# SkinProc_v0_1b.net
KiCad netlist of a schematic drawn in EAGLE
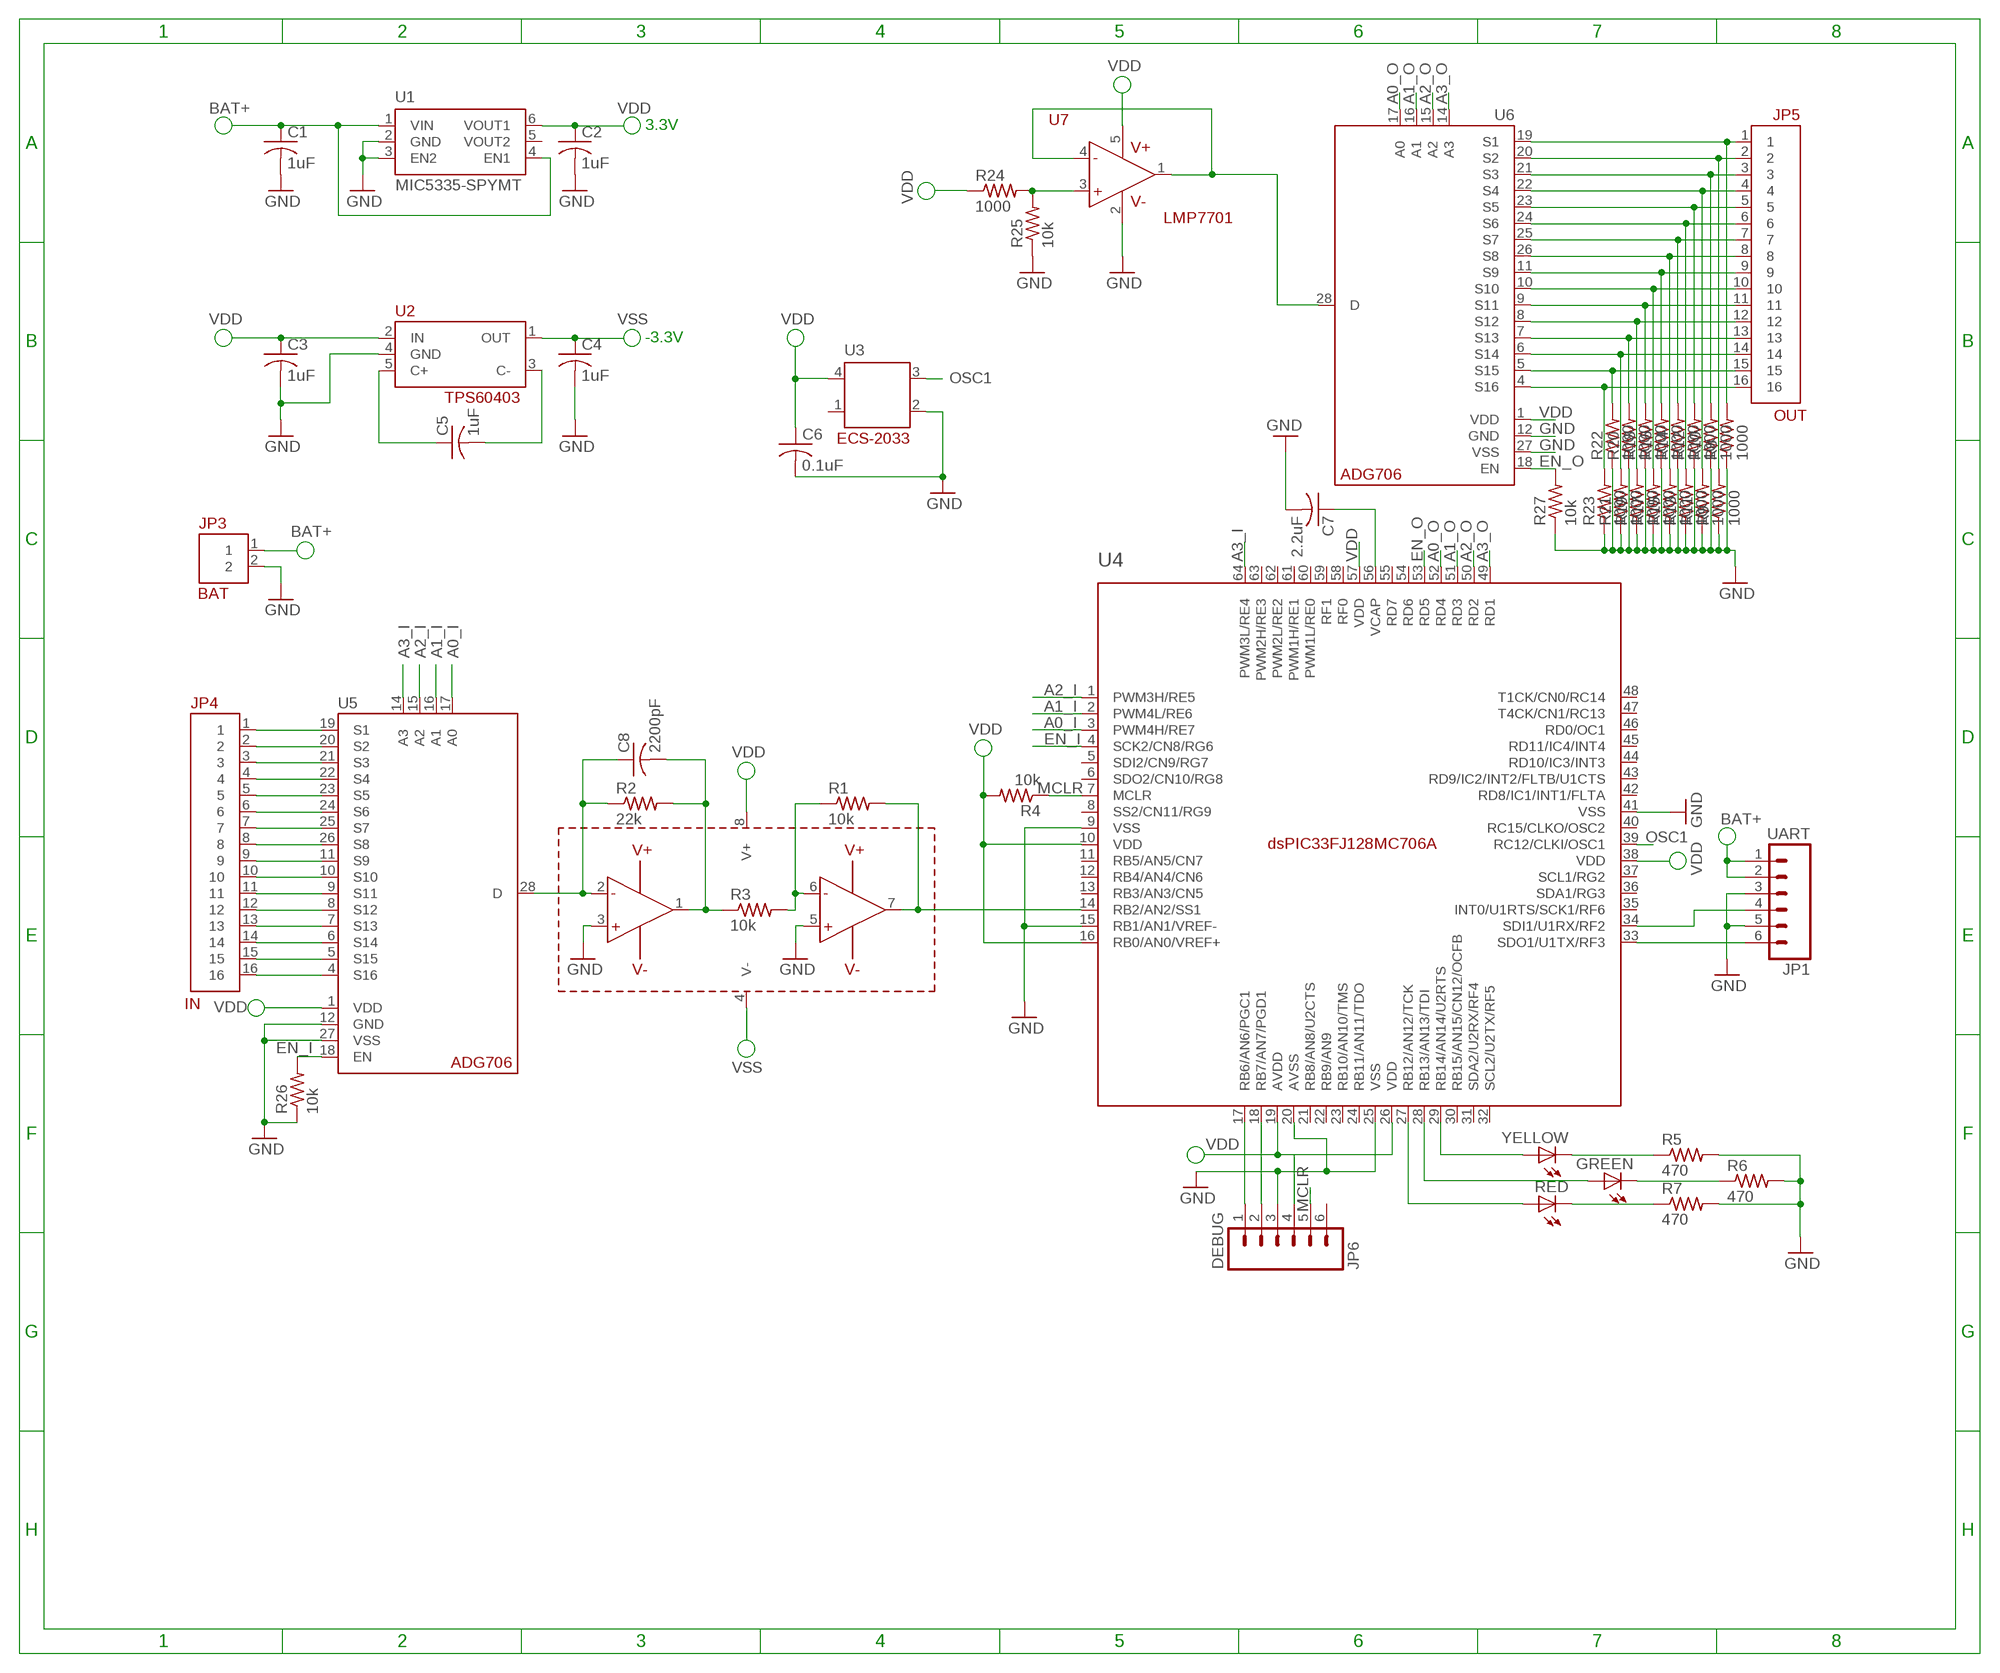
[diagram p0: schematic, sheet 1]

(export (version "E")
  (design (tool "Eeschema 10.0.6"))
  (components
    (comp (ref "C1")
      (value "1uF")
      (footprint "eagle-import:C0402")
      (libsource (lib "eagle-import") (part "C-USC0402"))
    )
    (comp (ref "C2")
      (value "1uF")
      (footprint "eagle-import:C0402")
      (libsource (lib "eagle-import") (part "C-USC0402"))
    )
    (comp (ref "C3")
      (value "1uF")
      (footprint "eagle-import:C0402")
      (libsource (lib "eagle-import") (part "C-USC0402"))
    )
    (comp (ref "C4")
      (value "1uF")
      (footprint "eagle-import:C0402")
      (libsource (lib "eagle-import") (part "C-USC0402"))
    )
    (comp (ref "C5")
      (value "1uF")
      (footprint "eagle-import:C0402")
      (libsource (lib "eagle-import") (part "C-USC0402"))
    )
    (comp (ref "C6")
      (value "0.1uF")
      (footprint "eagle-import:C0402")
      (libsource (lib "eagle-import") (part "C-USC0402"))
    )
    (comp (ref "C7")
      (value "2.2uF")
      (footprint "eagle-import:C0402")
      (libsource (lib "eagle-import") (part "C-USC0402"))
    )
    (comp (ref "C8")
      (value "2200pF")
      (footprint "eagle-import:C0402")
      (libsource (lib "eagle-import") (part "C-USC0402"))
    )
    (comp (ref "GREEN")
      (value "LEDCHIP-LED0603")
      (footprint "eagle-import:CHIP-LED0603")
      (libsource (lib "eagle-import") (part "LEDCHIP-LED0603"))
    )
    (comp (ref "JP1")
      (value "UART")
      (footprint "eagle-import:MOLEX_503480-0600")
      (libsource (lib "eagle-import") (part "MOLEX_503480-0600"))
    )
    (comp (ref "JP3")
      (value "BAT")
      (footprint "eagle-import:2_PAD")
      (libsource (lib "eagle-import") (part "2_PAD"))
    )
    (comp (ref "JP4")
      (value "IN")
      (footprint "eagle-import:16_PAD")
      (libsource (lib "eagle-import") (part "16_PAD"))
    )
    (comp (ref "JP5")
      (value "OUT")
      (footprint "eagle-import:16_PAD")
      (libsource (lib "eagle-import") (part "16_PAD"))
    )
    (comp (ref "JP6")
      (value "DEBUG")
      (footprint "eagle-import:MOLEX_503480-0600")
      (libsource (lib "eagle-import") (part "MOLEX_503480-0600"))
    )
    (comp (ref "R1")
      (value "10k")
      (footprint "eagle-import:R0402")
      (libsource (lib "eagle-import") (part "R-US_R0402"))
    )
    (comp (ref "R2")
      (value "22k")
      (footprint "eagle-import:R0402")
      (libsource (lib "eagle-import") (part "R-US_R0402"))
    )
    (comp (ref "R3")
      (value "10k")
      (footprint "eagle-import:R0402")
      (libsource (lib "eagle-import") (part "R-US_R0402"))
    )
    (comp (ref "R4")
      (value "10k")
      (footprint "eagle-import:R0402")
      (libsource (lib "eagle-import") (part "R-US_R0402"))
    )
    (comp (ref "R5")
      (value "470")
      (footprint "eagle-import:R0402")
      (libsource (lib "eagle-import") (part "R-US_R0402"))
    )
    (comp (ref "R6")
      (value "470")
      (footprint "eagle-import:R0402")
      (libsource (lib "eagle-import") (part "R-US_R0402"))
    )
    (comp (ref "R7")
      (value "470")
      (footprint "eagle-import:R0402")
      (libsource (lib "eagle-import") (part "R-US_R0402"))
    )
    (comp (ref "R8")
      (value "1000")
      (footprint "eagle-import:R0402")
      (libsource (lib "eagle-import") (part "R-US_R0402"))
    )
    (comp (ref "R9")
      (value "1000")
      (footprint "eagle-import:R0402")
      (libsource (lib "eagle-import") (part "R-US_R0402"))
    )
    (comp (ref "R10")
      (value "1000")
      (footprint "eagle-import:R0402")
      (libsource (lib "eagle-import") (part "R-US_R0402"))
    )
    (comp (ref "R11")
      (value "1000")
      (footprint "eagle-import:R0402")
      (libsource (lib "eagle-import") (part "R-US_R0402"))
    )
    (comp (ref "R12")
      (value "1000")
      (footprint "eagle-import:R0402")
      (libsource (lib "eagle-import") (part "R-US_R0402"))
    )
    (comp (ref "R13")
      (value "1000")
      (footprint "eagle-import:R0402")
      (libsource (lib "eagle-import") (part "R-US_R0402"))
    )
    (comp (ref "R14")
      (value "1000")
      (footprint "eagle-import:R0402")
      (libsource (lib "eagle-import") (part "R-US_R0402"))
    )
    (comp (ref "R15")
      (value "1000")
      (footprint "eagle-import:R0402")
      (libsource (lib "eagle-import") (part "R-US_R0402"))
    )
    (comp (ref "R16")
      (value "1000")
      (footprint "eagle-import:R0402")
      (libsource (lib "eagle-import") (part "R-US_R0402"))
    )
    (comp (ref "R17")
      (value "1000")
      (footprint "eagle-import:R0402")
      (libsource (lib "eagle-import") (part "R-US_R0402"))
    )
    (comp (ref "R18")
      (value "1000")
      (footprint "eagle-import:R0402")
      (libsource (lib "eagle-import") (part "R-US_R0402"))
    )
    (comp (ref "R19")
      (value "1000")
      (footprint "eagle-import:R0402")
      (libsource (lib "eagle-import") (part "R-US_R0402"))
    )
    (comp (ref "R20")
      (value "1000")
      (footprint "eagle-import:R0402")
      (libsource (lib "eagle-import") (part "R-US_R0402"))
    )
    (comp (ref "R21")
      (value "1000")
      (footprint "eagle-import:R0402")
      (libsource (lib "eagle-import") (part "R-US_R0402"))
    )
    (comp (ref "R22")
      (value "1000")
      (footprint "eagle-import:R0402")
      (libsource (lib "eagle-import") (part "R-US_R0402"))
    )
    (comp (ref "R23")
      (value "1000")
      (footprint "eagle-import:R0402")
      (libsource (lib "eagle-import") (part "R-US_R0402"))
    )
    (comp (ref "R24")
      (value "1000")
      (footprint "eagle-import:R0402")
      (libsource (lib "eagle-import") (part "R-US_R0402"))
    )
    (comp (ref "R25")
      (value "10k")
      (footprint "eagle-import:R0402")
      (libsource (lib "eagle-import") (part "R-US_R0402"))
    )
    (comp (ref "R26")
      (value "10k")
      (footprint "eagle-import:R0402")
      (libsource (lib "eagle-import") (part "R-US_R0402"))
    )
    (comp (ref "R27")
      (value "10k")
      (footprint "eagle-import:R0402")
      (libsource (lib "eagle-import") (part "R-US_R0402"))
    )
    (comp (ref "RED")
      (value "LEDCHIP-LED0603")
      (footprint "eagle-import:CHIP-LED0603")
      (libsource (lib "eagle-import") (part "LEDCHIP-LED0603"))
    )
    (comp (ref "U1")
      (value "MIC5335-SPYMT")
      (footprint "eagle-import:MLF-6")
      (libsource (lib "eagle-import") (part "MIC5320-JGYML"))
    )
    (comp (ref "U2")
      (value "TPS60403")
      (footprint "eagle-import:SOT23-DBV")
      (libsource (lib "eagle-import") (part "TPS60403"))
    )
    (comp (ref "U3")
      (value "OSCILLATORS")
      (footprint "eagle-import:OSCILLATOR-SMD")
      (libsource (lib "eagle-import") (part "OSCILLATORS"))
    )
    (comp (ref "U4")
      (value "DSPIC33FJ128MC706-I/PT")
      (footprint "eagle-import:TQFP64")
      (libsource (lib "eagle-import") (part "DSPIC33FJ128MC706-I/PT"))
    )
    (comp (ref "U5")
      (value "ADG706")
      (footprint "eagle-import:TSSOP28")
      (libsource (lib "eagle-import") (part "ADG706"))
    )
    (comp (ref "U6")
      (value "ADG706")
      (footprint "eagle-import:TSSOP28")
      (libsource (lib "eagle-import") (part "ADG706"))
    )
    (comp (ref "U7")
      (value "LMP7701")
      (footprint "eagle-import:SOT23-DBV")
      (libsource (lib "eagle-import") (part "NATIONAL_OP_AMP_SINGLE"))
    )
    (comp (ref "U8")
      (value "NATIONAL_OP_AMP")
      (footprint "eagle-import:SO08")
      (libsource (lib "eagle-import") (part "NATIONAL_OP_AMP"))
    )
    (comp (ref "YELLOW")
      (value "LEDCHIP-LED0603")
      (footprint "eagle-import:CHIP-LED0603")
      (libsource (lib "eagle-import") (part "LEDCHIP-LED0603"))
    )
  )
  (nets
    (net (code "1") (name "/A0_I") (class "Default")
      (node (ref "U4") (pin "3") (pinfunction "PWM4H/RE7_3") (pintype "bidirectional"))
      (node (ref "U5") (pin "17") (pinfunction "A0_17") (pintype "bidirectional"))
    )
    (net (code "2") (name "/A0_O") (class "Default")
      (node (ref "U4") (pin "52") (pinfunction "RD4_52") (pintype "bidirectional"))
      (node (ref "U6") (pin "17") (pinfunction "A0_17") (pintype "bidirectional"))
    )
    (net (code "3") (name "/A1_I") (class "Default")
      (node (ref "U4") (pin "2") (pinfunction "PWM4L/RE6_2") (pintype "bidirectional"))
      (node (ref "U5") (pin "16") (pinfunction "A1_16") (pintype "bidirectional"))
    )
    (net (code "4") (name "/A1_O") (class "Default")
      (node (ref "U4") (pin "51") (pinfunction "RD3_51") (pintype "bidirectional"))
      (node (ref "U6") (pin "16") (pinfunction "A1_16") (pintype "bidirectional"))
    )
    (net (code "5") (name "/A2_I") (class "Default")
      (node (ref "U4") (pin "1") (pinfunction "PWM3H/RE5_1") (pintype "bidirectional"))
      (node (ref "U5") (pin "15") (pinfunction "A2_15") (pintype "bidirectional"))
    )
    (net (code "6") (name "/A2_O") (class "Default")
      (node (ref "U4") (pin "50") (pinfunction "RD2_50") (pintype "bidirectional"))
      (node (ref "U6") (pin "15") (pinfunction "A2_15") (pintype "bidirectional"))
    )
    (net (code "7") (name "/A3_I") (class "Default")
      (node (ref "U4") (pin "64") (pinfunction "PWM3L/RE4_64") (pintype "bidirectional"))
      (node (ref "U5") (pin "14") (pinfunction "A3_14") (pintype "bidirectional"))
    )
    (net (code "8") (name "/A3_O") (class "Default")
      (node (ref "U4") (pin "49") (pinfunction "RD1_49") (pintype "bidirectional"))
      (node (ref "U6") (pin "14") (pinfunction "A3_14") (pintype "bidirectional"))
    )
    (net (code "9") (name "/BAT+") (class "Default")
      (node (ref "C1") (pin "1") (pinfunction "1_1") (pintype "passive"))
      (node (ref "JP1") (pin "1") (pinfunction "1_1") (pintype "passive"))
      (node (ref "JP1") (pin "2") (pinfunction "2_2") (pintype "passive"))
      (node (ref "JP3") (pin "1") (pinfunction "1_1") (pintype "bidirectional"))
      (node (ref "U1") (pin "1") (pinfunction "VIN_1") (pintype "bidirectional"))
      (node (ref "U1") (pin "4") (pinfunction "EN1_4") (pintype "bidirectional"))
    )
    (net (code "10") (name "/EN_I") (class "Default")
      (node (ref "R26") (pin "2") (pinfunction "2_2") (pintype "passive"))
      (node (ref "U4") (pin "4") (pinfunction "SCK2/CN8/RG6_4") (pintype "bidirectional"))
      (node (ref "U5") (pin "18") (pinfunction "EN_18") (pintype "bidirectional"))
    )
    (net (code "11") (name "/EN_O") (class "Default")
      (node (ref "R27") (pin "2") (pinfunction "2_2") (pintype "passive"))
      (node (ref "U4") (pin "53") (pinfunction "RD5_53") (pintype "bidirectional"))
      (node (ref "U6") (pin "18") (pinfunction "EN_18") (pintype "bidirectional"))
    )
    (net (code "12") (name "/MCLR") (class "Default")
      (node (ref "JP6") (pin "5") (pinfunction "5_5") (pintype "passive"))
      (node (ref "R4") (pin "1") (pinfunction "1_1") (pintype "passive"))
      (node (ref "U4") (pin "7") (pinfunction "MCLR_7") (pintype "input"))
    )
    (net (code "13") (name "/OSC1") (class "Default")
      (node (ref "U3") (pin "3") (pinfunction "OUT_3") (pintype "bidirectional"))
      (node (ref "U4") (pin "39") (pinfunction "RC12/CLKI/OSC1_39") (pintype "bidirectional"))
    )
    (net (code "14") (name "/VDD") (class "Default")
      (node (ref "C2") (pin "1") (pinfunction "1_1") (pintype "passive"))
      (node (ref "C3") (pin "1") (pinfunction "1_1") (pintype "passive"))
      (node (ref "C6") (pin "1") (pinfunction "1_1") (pintype "passive"))
      (node (ref "JP6") (pin "4") (pinfunction "4_4") (pintype "passive"))
      (node (ref "R24") (pin "1") (pinfunction "1_1") (pintype "passive"))
      (node (ref "R4") (pin "2") (pinfunction "2_2") (pintype "passive"))
      (node (ref "U1") (pin "6") (pinfunction "VOUT1_6") (pintype "bidirectional"))
      (node (ref "U2") (pin "2") (pinfunction "IN_2") (pintype "bidirectional"))
      (node (ref "U3") (pin "4") (pinfunction "VDD_4") (pintype "bidirectional"))
      (node (ref "U4") (pin "10") (pinfunction "VDD_10") (pintype "power_in"))
      (node (ref "U4") (pin "16") (pinfunction "RB0/AN0/VREF+_16") (pintype "bidirectional"))
      (node (ref "U4") (pin "19") (pinfunction "AVDD_19") (pintype "power_in"))
      (node (ref "U4") (pin "26") (pinfunction "VDD_26") (pintype "power_in"))
      (node (ref "U4") (pin "38") (pinfunction "VDD_38") (pintype "power_in"))
      (node (ref "U4") (pin "57") (pinfunction "VDD_57") (pintype "power_in"))
      (node (ref "U5") (pin "1") (pinfunction "VDD_1") (pintype "bidirectional"))
      (node (ref "U6") (pin "1") (pinfunction "VDD_1") (pintype "bidirectional"))
      (node (ref "U7") (pin "5") (pinfunction "V+_5") (pintype "bidirectional"))
      (node (ref "U8") (pin "8") (pinfunction "V+_8") (pintype "bidirectional"))
    )
    (net (code "15") (name "/VSS") (class "Default")
      (node (ref "C4") (pin "1") (pinfunction "1_1") (pintype "passive"))
      (node (ref "U2") (pin "1") (pinfunction "OUT_1") (pintype "bidirectional"))
      (node (ref "U8") (pin "4") (pinfunction "V-_4") (pintype "bidirectional"))
    )
    (net (code "16") (name "GND") (class "Default")
      (node (ref "C1") (pin "2") (pinfunction "2_2") (pintype "passive"))
      (node (ref "C2") (pin "2") (pinfunction "2_2") (pintype "passive"))
      (node (ref "C3") (pin "2") (pinfunction "2_2") (pintype "passive"))
      (node (ref "C4") (pin "2") (pinfunction "2_2") (pintype "passive"))
      (node (ref "C6") (pin "2") (pinfunction "2_2") (pintype "passive"))
      (node (ref "C7") (pin "2") (pinfunction "2_2") (pintype "passive"))
      (node (ref "JP1") (pin "3") (pinfunction "3_3") (pintype "passive"))
      (node (ref "JP1") (pin "5") (pinfunction "5_5") (pintype "passive"))
      (node (ref "JP3") (pin "2") (pinfunction "2_2") (pintype "bidirectional"))
      (node (ref "JP6") (pin "3") (pinfunction "3_3") (pintype "passive"))
      (node (ref "R10") (pin "1") (pinfunction "1_1") (pintype "passive"))
      (node (ref "R11") (pin "1") (pinfunction "1_1") (pintype "passive"))
      (node (ref "R12") (pin "1") (pinfunction "1_1") (pintype "passive"))
      (node (ref "R13") (pin "1") (pinfunction "1_1") (pintype "passive"))
      (node (ref "R14") (pin "1") (pinfunction "1_1") (pintype "passive"))
      (node (ref "R15") (pin "1") (pinfunction "1_1") (pintype "passive"))
      (node (ref "R16") (pin "1") (pinfunction "1_1") (pintype "passive"))
      (node (ref "R17") (pin "1") (pinfunction "1_1") (pintype "passive"))
      (node (ref "R18") (pin "1") (pinfunction "1_1") (pintype "passive"))
      (node (ref "R19") (pin "1") (pinfunction "1_1") (pintype "passive"))
      (node (ref "R20") (pin "1") (pinfunction "1_1") (pintype "passive"))
      (node (ref "R21") (pin "1") (pinfunction "1_1") (pintype "passive"))
      (node (ref "R22") (pin "1") (pinfunction "1_1") (pintype "passive"))
      (node (ref "R23") (pin "1") (pinfunction "1_1") (pintype "passive"))
      (node (ref "R25") (pin "1") (pinfunction "1_1") (pintype "passive"))
      (node (ref "R26") (pin "1") (pinfunction "1_1") (pintype "passive"))
      (node (ref "R27") (pin "1") (pinfunction "1_1") (pintype "passive"))
      (node (ref "R5") (pin "2") (pinfunction "2_2") (pintype "passive"))
      (node (ref "R6") (pin "2") (pinfunction "2_2") (pintype "passive"))
      (node (ref "R7") (pin "2") (pinfunction "2_2") (pintype "passive"))
      (node (ref "R8") (pin "1") (pinfunction "1_1") (pintype "passive"))
      (node (ref "R9") (pin "1") (pinfunction "1_1") (pintype "passive"))
      (node (ref "U1") (pin "2") (pinfunction "GND_2") (pintype "bidirectional"))
      (node (ref "U1") (pin "3") (pinfunction "EN2_3") (pintype "bidirectional"))
      (node (ref "U2") (pin "4") (pinfunction "GND_4") (pintype "bidirectional"))
      (node (ref "U3") (pin "2") (pinfunction "GND_2") (pintype "bidirectional"))
      (node (ref "U4") (pin "15") (pinfunction "RB1/AN1/VREF-_15") (pintype "bidirectional"))
      (node (ref "U4") (pin "20") (pinfunction "AVSS_20") (pintype "power_in"))
      (node (ref "U4") (pin "25") (pinfunction "VSS_25") (pintype "power_in"))
      (node (ref "U4") (pin "41") (pinfunction "VSS_41") (pintype "power_in"))
      (node (ref "U4") (pin "9") (pinfunction "VSS_9") (pintype "power_in"))
      (node (ref "U5") (pin "12") (pinfunction "GND_12") (pintype "bidirectional"))
      (node (ref "U5") (pin "27") (pinfunction "VSS_27") (pintype "bidirectional"))
      (node (ref "U6") (pin "12") (pinfunction "GND_12") (pintype "bidirectional"))
      (node (ref "U6") (pin "27") (pinfunction "VSS_27") (pintype "bidirectional"))
      (node (ref "U7") (pin "2") (pinfunction "V-_2") (pintype "bidirectional"))
      (node (ref "U8") (pin "3") (pinfunction "+A_3") (pintype "bidirectional"))
      (node (ref "U8") (pin "5") (pinfunction "+B_5") (pintype "bidirectional"))
    )
    (net (code "17") (name "Net-(GREEN-PadC)") (class "Default")
      (node (ref "GREEN") (pin "C") (pinfunction "C_C") (pintype "passive"))
      (node (ref "R6") (pin "1") (pinfunction "1_1") (pintype "passive"))
    )
    (net (code "18") (name "Net-(R5-Pad1)") (class "Default")
      (node (ref "R5") (pin "1") (pinfunction "1_1") (pintype "passive"))
      (node (ref "YELLOW") (pin "C") (pinfunction "C_C") (pintype "passive"))
    )
    (net (code "19") (name "Net-(R7-Pad1)") (class "Default")
      (node (ref "R7") (pin "1") (pinfunction "1_1") (pintype "passive"))
      (node (ref "RED") (pin "C") (pinfunction "C_C") (pintype "passive"))
    )
    (net (code "20") (name "Net-(U2-C+)") (class "Default")
      (node (ref "C5") (pin "1") (pinfunction "1_1") (pintype "passive"))
      (node (ref "U2") (pin "5") (pinfunction "C+_5") (pintype "bidirectional"))
    )
    (net (code "21") (name "Net-(U2-C-)") (class "Default")
      (node (ref "C5") (pin "2") (pinfunction "2_2") (pintype "passive"))
      (node (ref "U2") (pin "3") (pinfunction "C-_3") (pintype "bidirectional"))
    )
    (net (code "22") (name "Net-(U4-RB2{slash}AN2{slash}SS1)") (class "Default")
      (node (ref "R1") (pin "2") (pinfunction "2_2") (pintype "passive"))
      (node (ref "U4") (pin "14") (pinfunction "RB2/AN2/SS1_14") (pintype "bidirectional"))
      (node (ref "U8") (pin "7") (pinfunction "VOUTB_7") (pintype "bidirectional"))
    )
    (net (code "23") (name "Net-(U4-RB6{slash}AN6{slash}PGC1)") (class "Default")
      (node (ref "JP6") (pin "1") (pinfunction "1_1") (pintype "passive"))
      (node (ref "U4") (pin "17") (pinfunction "RB6/AN6/PGC1_17") (pintype "bidirectional"))
    )
    (net (code "24") (name "Net-(U4-RB7{slash}AN7{slash}PGD1)") (class "Default")
      (node (ref "JP6") (pin "2") (pinfunction "2_2") (pintype "passive"))
      (node (ref "U4") (pin "18") (pinfunction "RB7/AN7/PGD1_18") (pintype "bidirectional"))
    )
    (net (code "25") (name "Net-(U4-RB12{slash}AN12{slash}TCK)") (class "Default")
      (node (ref "RED") (pin "A") (pinfunction "A_A") (pintype "passive"))
      (node (ref "U4") (pin "27") (pinfunction "RB12/AN12/TCK_27") (pintype "bidirectional"))
    )
    (net (code "26") (name "Net-(U4-RB13{slash}AN13{slash}TDI)") (class "Default")
      (node (ref "GREEN") (pin "A") (pinfunction "A_A") (pintype "passive"))
      (node (ref "U4") (pin "28") (pinfunction "RB13/AN13/TDI_28") (pintype "bidirectional"))
    )
    (net (code "27") (name "Net-(U4-RB14{slash}AN14{slash}U2RTS)") (class "Default")
      (node (ref "U4") (pin "29") (pinfunction "RB14/AN14/U2RTS_29") (pintype "bidirectional"))
      (node (ref "YELLOW") (pin "A") (pinfunction "A_A") (pintype "passive"))
    )
    (net (code "28") (name "Net-(U4-SDI1{slash}U1RX{slash}RF2)") (class "Default")
      (node (ref "JP1") (pin "4") (pinfunction "4_4") (pintype "passive"))
      (node (ref "U4") (pin "34") (pinfunction "SDI1/U1RX/RF2_34") (pintype "bidirectional"))
    )
    (net (code "29") (name "Net-(U4-SDO1{slash}U1TX{slash}RF3)") (class "Default")
      (node (ref "JP1") (pin "6") (pinfunction "6_6") (pintype "passive"))
      (node (ref "U4") (pin "33") (pinfunction "SDO1/U1TX/RF3_33") (pintype "bidirectional"))
    )
    (net (code "30") (name "Net-(U4-VCAP)") (class "Default")
      (node (ref "C7") (pin "1") (pinfunction "1_1") (pintype "passive"))
      (node (ref "U4") (pin "56") (pinfunction "VCAP_56") (pintype "power_in"))
    )
    (net (code "31") (name "Net-(U5-D)") (class "Default")
      (node (ref "C8") (pin "1") (pinfunction "1_1") (pintype "passive"))
      (node (ref "R2") (pin "1") (pinfunction "1_1") (pintype "passive"))
      (node (ref "U5") (pin "28") (pinfunction "D_28") (pintype "bidirectional"))
      (node (ref "U8") (pin "2") (pinfunction "-A_2") (pintype "bidirectional"))
    )
    (net (code "32") (name "Net-(U5-S1)") (class "Default")
      (node (ref "JP4") (pin "1") (pinfunction "1_1") (pintype "bidirectional"))
      (node (ref "U5") (pin "19") (pinfunction "S1_19") (pintype "bidirectional"))
    )
    (net (code "33") (name "Net-(U5-S2)") (class "Default")
      (node (ref "JP4") (pin "2") (pinfunction "2_2") (pintype "bidirectional"))
      (node (ref "U5") (pin "20") (pinfunction "S2_20") (pintype "bidirectional"))
    )
    (net (code "34") (name "Net-(U5-S3)") (class "Default")
      (node (ref "JP4") (pin "3") (pinfunction "3_3") (pintype "bidirectional"))
      (node (ref "U5") (pin "21") (pinfunction "S3_21") (pintype "bidirectional"))
    )
    (net (code "35") (name "Net-(U5-S4)") (class "Default")
      (node (ref "JP4") (pin "4") (pinfunction "4_4") (pintype "bidirectional"))
      (node (ref "U5") (pin "22") (pinfunction "S4_22") (pintype "bidirectional"))
    )
    (net (code "36") (name "Net-(U5-S5)") (class "Default")
      (node (ref "JP4") (pin "5") (pinfunction "5_5") (pintype "bidirectional"))
      (node (ref "U5") (pin "23") (pinfunction "S5_23") (pintype "bidirectional"))
    )
    (net (code "37") (name "Net-(U5-S6)") (class "Default")
      (node (ref "JP4") (pin "6") (pinfunction "6_6") (pintype "bidirectional"))
      (node (ref "U5") (pin "24") (pinfunction "S6_24") (pintype "bidirectional"))
    )
    (net (code "38") (name "Net-(U5-S7)") (class "Default")
      (node (ref "JP4") (pin "7") (pinfunction "7_7") (pintype "bidirectional"))
      (node (ref "U5") (pin "25") (pinfunction "S7_25") (pintype "bidirectional"))
    )
    (net (code "39") (name "Net-(U5-S8)") (class "Default")
      (node (ref "JP4") (pin "8") (pinfunction "8_8") (pintype "bidirectional"))
      (node (ref "U5") (pin "26") (pinfunction "S8_26") (pintype "bidirectional"))
    )
    (net (code "40") (name "Net-(U5-S9)") (class "Default")
      (node (ref "JP4") (pin "9") (pinfunction "9_9") (pintype "bidirectional"))
      (node (ref "U5") (pin "11") (pinfunction "S9_11") (pintype "bidirectional"))
    )
    (net (code "41") (name "Net-(U5-S10)") (class "Default")
      (node (ref "JP4") (pin "10") (pinfunction "10_10") (pintype "bidirectional"))
      (node (ref "U5") (pin "10") (pinfunction "S10_10") (pintype "bidirectional"))
    )
    (net (code "42") (name "Net-(U5-S11)") (class "Default")
      (node (ref "JP4") (pin "11") (pinfunction "11_11") (pintype "bidirectional"))
      (node (ref "U5") (pin "9") (pinfunction "S11_9") (pintype "bidirectional"))
    )
    (net (code "43") (name "Net-(U5-S12)") (class "Default")
      (node (ref "JP4") (pin "12") (pinfunction "12_12") (pintype "bidirectional"))
      (node (ref "U5") (pin "8") (pinfunction "S12_8") (pintype "bidirectional"))
    )
    (net (code "44") (name "Net-(U5-S13)") (class "Default")
      (node (ref "JP4") (pin "13") (pinfunction "13_13") (pintype "bidirectional"))
      (node (ref "U5") (pin "7") (pinfunction "S13_7") (pintype "bidirectional"))
    )
    (net (code "45") (name "Net-(U5-S14)") (class "Default")
      (node (ref "JP4") (pin "14") (pinfunction "14_14") (pintype "bidirectional"))
      (node (ref "U5") (pin "6") (pinfunction "S14_6") (pintype "bidirectional"))
    )
    (net (code "46") (name "Net-(U5-S15)") (class "Default")
      (node (ref "JP4") (pin "15") (pinfunction "15_15") (pintype "bidirectional"))
      (node (ref "U5") (pin "5") (pinfunction "S15_5") (pintype "bidirectional"))
    )
    (net (code "47") (name "Net-(U5-S16)") (class "Default")
      (node (ref "JP4") (pin "16") (pinfunction "16_16") (pintype "bidirectional"))
      (node (ref "U5") (pin "4") (pinfunction "S16_4") (pintype "bidirectional"))
    )
    (net (code "48") (name "Net-(U6-D)") (class "Default")
      (node (ref "U6") (pin "28") (pinfunction "D_28") (pintype "bidirectional"))
      (node (ref "U7") (pin "1") (pinfunction "VOUT_1") (pintype "bidirectional"))
      (node (ref "U7") (pin "4") (pinfunction "-_4") (pintype "bidirectional"))
    )
    (net (code "49") (name "Net-(U6-S1)") (class "Default")
      (node (ref "JP5") (pin "1") (pinfunction "1_1") (pintype "bidirectional"))
      (node (ref "R8") (pin "2") (pinfunction "2_2") (pintype "passive"))
      (node (ref "U6") (pin "19") (pinfunction "S1_19") (pintype "bidirectional"))
    )
    (net (code "50") (name "Net-(U6-S2)") (class "Default")
      (node (ref "JP5") (pin "2") (pinfunction "2_2") (pintype "bidirectional"))
      (node (ref "R9") (pin "2") (pinfunction "2_2") (pintype "passive"))
      (node (ref "U6") (pin "20") (pinfunction "S2_20") (pintype "bidirectional"))
    )
    (net (code "51") (name "Net-(U6-S3)") (class "Default")
      (node (ref "JP5") (pin "3") (pinfunction "3_3") (pintype "bidirectional"))
      (node (ref "R10") (pin "2") (pinfunction "2_2") (pintype "passive"))
      (node (ref "U6") (pin "21") (pinfunction "S3_21") (pintype "bidirectional"))
    )
    (net (code "52") (name "Net-(U6-S4)") (class "Default")
      (node (ref "JP5") (pin "4") (pinfunction "4_4") (pintype "bidirectional"))
      (node (ref "R11") (pin "2") (pinfunction "2_2") (pintype "passive"))
      (node (ref "U6") (pin "22") (pinfunction "S4_22") (pintype "bidirectional"))
    )
    (net (code "53") (name "Net-(U6-S5)") (class "Default")
      (node (ref "JP5") (pin "5") (pinfunction "5_5") (pintype "bidirectional"))
      (node (ref "R12") (pin "2") (pinfunction "2_2") (pintype "passive"))
      (node (ref "U6") (pin "23") (pinfunction "S5_23") (pintype "bidirectional"))
    )
    (net (code "54") (name "Net-(U6-S6)") (class "Default")
      (node (ref "JP5") (pin "6") (pinfunction "6_6") (pintype "bidirectional"))
      (node (ref "R13") (pin "2") (pinfunction "2_2") (pintype "passive"))
      (node (ref "U6") (pin "24") (pinfunction "S6_24") (pintype "bidirectional"))
    )
    (net (code "55") (name "Net-(U6-S7)") (class "Default")
      (node (ref "JP5") (pin "7") (pinfunction "7_7") (pintype "bidirectional"))
      (node (ref "R14") (pin "2") (pinfunction "2_2") (pintype "passive"))
      (node (ref "U6") (pin "25") (pinfunction "S7_25") (pintype "bidirectional"))
    )
    (net (code "56") (name "Net-(U6-S8)") (class "Default")
      (node (ref "JP5") (pin "8") (pinfunction "8_8") (pintype "bidirectional"))
      (node (ref "R15") (pin "2") (pinfunction "2_2") (pintype "passive"))
      (node (ref "U6") (pin "26") (pinfunction "S8_26") (pintype "bidirectional"))
    )
    (net (code "57") (name "Net-(U6-S9)") (class "Default")
      (node (ref "JP5") (pin "9") (pinfunction "9_9") (pintype "bidirectional"))
      (node (ref "R16") (pin "2") (pinfunction "2_2") (pintype "passive"))
      (node (ref "U6") (pin "11") (pinfunction "S9_11") (pintype "bidirectional"))
    )
    (net (code "58") (name "Net-(U6-S10)") (class "Default")
      (node (ref "JP5") (pin "10") (pinfunction "10_10") (pintype "bidirectional"))
      (node (ref "R17") (pin "2") (pinfunction "2_2") (pintype "passive"))
      (node (ref "U6") (pin "10") (pinfunction "S10_10") (pintype "bidirectional"))
    )
    (net (code "59") (name "Net-(U6-S11)") (class "Default")
      (node (ref "JP5") (pin "11") (pinfunction "11_11") (pintype "bidirectional"))
      (node (ref "R18") (pin "2") (pinfunction "2_2") (pintype "passive"))
      (node (ref "U6") (pin "9") (pinfunction "S11_9") (pintype "bidirectional"))
    )
    (net (code "60") (name "Net-(U6-S12)") (class "Default")
      (node (ref "JP5") (pin "12") (pinfunction "12_12") (pintype "bidirectional"))
      (node (ref "R19") (pin "2") (pinfunction "2_2") (pintype "passive"))
      (node (ref "U6") (pin "8") (pinfunction "S12_8") (pintype "bidirectional"))
    )
    (net (code "61") (name "Net-(U6-S13)") (class "Default")
      (node (ref "JP5") (pin "13") (pinfunction "13_13") (pintype "bidirectional"))
      (node (ref "R20") (pin "2") (pinfunction "2_2") (pintype "passive"))
      (node (ref "U6") (pin "7") (pinfunction "S13_7") (pintype "bidirectional"))
    )
    (net (code "62") (name "Net-(U6-S14)") (class "Default")
      (node (ref "JP5") (pin "14") (pinfunction "14_14") (pintype "bidirectional"))
      (node (ref "R21") (pin "2") (pinfunction "2_2") (pintype "passive"))
      (node (ref "U6") (pin "6") (pinfunction "S14_6") (pintype "bidirectional"))
    )
    (net (code "63") (name "Net-(U6-S15)") (class "Default")
      (node (ref "JP5") (pin "15") (pinfunction "15_15") (pintype "bidirectional"))
      (node (ref "R22") (pin "2") (pinfunction "2_2") (pintype "passive"))
      (node (ref "U6") (pin "5") (pinfunction "S15_5") (pintype "bidirectional"))
    )
    (net (code "64") (name "Net-(U6-S16)") (class "Default")
      (node (ref "JP5") (pin "16") (pinfunction "16_16") (pintype "bidirectional"))
      (node (ref "R23") (pin "2") (pinfunction "2_2") (pintype "passive"))
      (node (ref "U6") (pin "4") (pinfunction "S16_4") (pintype "bidirectional"))
    )
    (net (code "65") (name "Net-(U7-+)") (class "Default")
      (node (ref "R24") (pin "2") (pinfunction "2_2") (pintype "passive"))
      (node (ref "R25") (pin "2") (pinfunction "2_2") (pintype "passive"))
      (node (ref "U7") (pin "3") (pinfunction "+_3") (pintype "bidirectional"))
    )
    (net (code "66") (name "Net-(U8--B)") (class "Default")
      (node (ref "R1") (pin "1") (pinfunction "1_1") (pintype "passive"))
      (node (ref "R3") (pin "2") (pinfunction "2_2") (pintype "passive"))
      (node (ref "U8") (pin "6") (pinfunction "-B_6") (pintype "bidirectional"))
    )
    (net (code "67") (name "Net-(U8-VOUTA)") (class "Default")
      (node (ref "C8") (pin "2") (pinfunction "2_2") (pintype "passive"))
      (node (ref "R2") (pin "2") (pinfunction "2_2") (pintype "passive"))
      (node (ref "R3") (pin "1") (pinfunction "1_1") (pintype "passive"))
      (node (ref "U8") (pin "1") (pinfunction "VOUTA_1") (pintype "bidirectional"))
    )
    (net (code "68") (name "unconnected-(JP6-Pad6)") (class "Default")
      (node (ref "JP6") (pin "6") (pinfunction "6_6") (pintype "passive"))
    )
    (net (code "69") (name "unconnected-(U1-VOUT2-Pad5)") (class "Default")
      (node (ref "U1") (pin "5") (pinfunction "VOUT2_5") (pintype "bidirectional"))
    )
    (net (code "70") (name "unconnected-(U3-NC-Pad1)") (class "Default")
      (node (ref "U3") (pin "1") (pinfunction "NC_1") (pintype "bidirectional"))
    )
    (net (code "71") (name "unconnected-(U4-INT0{slash}U1RTS{slash}SCK1{slash}RF6-Pad35)") (class "Default")
      (node (ref "U4") (pin "35") (pinfunction "INT0/U1RTS/SCK1/RF6_35") (pintype "bidirectional"))
    )
    (net (code "72") (name "unconnected-(U4-PWM1H{slash}RE1-Pad61)") (class "Default")
      (node (ref "U4") (pin "61") (pinfunction "PWM1H/RE1_61") (pintype "bidirectional"))
    )
    (net (code "73") (name "unconnected-(U4-PWM1L{slash}RE0-Pad60)") (class "Default")
      (node (ref "U4") (pin "60") (pinfunction "PWM1L/RE0_60") (pintype "bidirectional"))
    )
    (net (code "74") (name "unconnected-(U4-PWM2H{slash}RE3-Pad63)") (class "Default")
      (node (ref "U4") (pin "63") (pinfunction "PWM2H/RE3_63") (pintype "bidirectional"))
    )
    (net (code "75") (name "unconnected-(U4-PWM2L{slash}RE2-Pad62)") (class "Default")
      (node (ref "U4") (pin "62") (pinfunction "PWM2L/RE2_62") (pintype "bidirectional"))
    )
    (net (code "76") (name "unconnected-(U4-RB3{slash}AN3{slash}CN5-Pad13)") (class "Default")
      (node (ref "U4") (pin "13") (pinfunction "RB3/AN3/CN5_13") (pintype "bidirectional"))
    )
    (net (code "77") (name "unconnected-(U4-RB4{slash}AN4{slash}CN6-Pad12)") (class "Default")
      (node (ref "U4") (pin "12") (pinfunction "RB4/AN4/CN6_12") (pintype "bidirectional"))
    )
    (net (code "78") (name "unconnected-(U4-RB5{slash}AN5{slash}CN7-Pad11)") (class "Default")
      (node (ref "U4") (pin "11") (pinfunction "RB5/AN5/CN7_11") (pintype "bidirectional"))
    )
    (net (code "79") (name "unconnected-(U4-RB8{slash}AN8{slash}U2CTS-Pad21)") (class "Default")
      (node (ref "U4") (pin "21") (pinfunction "RB8/AN8/U2CTS_21") (pintype "bidirectional"))
    )
    (net (code "80") (name "unconnected-(U4-RB9{slash}AN9-Pad22)") (class "Default")
      (node (ref "U4") (pin "22") (pinfunction "RB9/AN9_22") (pintype "bidirectional"))
    )
    (net (code "81") (name "unconnected-(U4-RB10{slash}AN10{slash}TMS-Pad23)") (class "Default")
      (node (ref "U4") (pin "23") (pinfunction "RB10/AN10/TMS_23") (pintype "bidirectional"))
    )
    (net (code "82") (name "unconnected-(U4-RB11{slash}AN11{slash}TDO-Pad24)") (class "Default")
      (node (ref "U4") (pin "24") (pinfunction "RB11/AN11/TDO_24") (pintype "bidirectional"))
    )
    (net (code "83") (name "unconnected-(U4-RB15{slash}AN15{slash}CN12{slash}OCFB-Pad30)") (class "Default")
      (node (ref "U4") (pin "30") (pinfunction "RB15/AN15/CN12/OCFB_30") (pintype "bidirectional"))
    )
    (net (code "84") (name "unconnected-(U4-RC15{slash}CLKO{slash}OSC2-Pad40)") (class "Default")
      (node (ref "U4") (pin "40") (pinfunction "RC15/CLKO/OSC2_40") (pintype "bidirectional"))
    )
    (net (code "85") (name "unconnected-(U4-RD0{slash}OC1-Pad46)") (class "Default")
      (node (ref "U4") (pin "46") (pinfunction "RD0/OC1_46") (pintype "bidirectional"))
    )
    (net (code "86") (name "unconnected-(U4-RD6-Pad54)") (class "Default")
      (node (ref "U4") (pin "54") (pinfunction "RD6_54") (pintype "bidirectional"))
    )
    (net (code "87") (name "unconnected-(U4-RD7-Pad55)") (class "Default")
      (node (ref "U4") (pin "55") (pinfunction "RD7_55") (pintype "bidirectional"))
    )
    (net (code "88") (name "unconnected-(U4-RD8{slash}IC1{slash}INT1{slash}FLTA-Pad42)") (class "Default")
      (node (ref "U4") (pin "42") (pinfunction "RD8/IC1/INT1/FLTA_42") (pintype "bidirectional"))
    )
    (net (code "89") (name "unconnected-(U4-RD9{slash}IC2{slash}INT2{slash}FLTB{slash}U1CTS-Pad43)") (class "Default")
      (node (ref "U4") (pin "43") (pinfunction "RD9/IC2/INT2/FLTB/U1CTS_43") (pintype "bidirectional"))
    )
    (net (code "90") (name "unconnected-(U4-RD10{slash}IC3{slash}INT3-Pad44)") (class "Default")
      (node (ref "U4") (pin "44") (pinfunction "RD10/IC3/INT3_44") (pintype "bidirectional"))
    )
    (net (code "91") (name "unconnected-(U4-RD11{slash}IC4{slash}INT4-Pad45)") (class "Default")
      (node (ref "U4") (pin "45") (pinfunction "RD11/IC4/INT4_45") (pintype "bidirectional"))
    )
    (net (code "92") (name "unconnected-(U4-RF0-Pad58)") (class "Default")
      (node (ref "U4") (pin "58") (pinfunction "RF0_58") (pintype "bidirectional"))
    )
    (net (code "93") (name "unconnected-(U4-RF1-Pad59)") (class "Default")
      (node (ref "U4") (pin "59") (pinfunction "RF1_59") (pintype "bidirectional"))
    )
    (net (code "94") (name "unconnected-(U4-SCL1{slash}RG2-Pad37)") (class "Default")
      (node (ref "U4") (pin "37") (pinfunction "SCL1/RG2_37") (pintype "bidirectional"))
    )
    (net (code "95") (name "unconnected-(U4-SCL2{slash}U2TX{slash}RF5-Pad32)") (class "Default")
      (node (ref "U4") (pin "32") (pinfunction "SCL2/U2TX/RF5_32") (pintype "bidirectional"))
    )
    (net (code "96") (name "unconnected-(U4-SDA1{slash}RG3-Pad36)") (class "Default")
      (node (ref "U4") (pin "36") (pinfunction "SDA1/RG3_36") (pintype "bidirectional"))
    )
    (net (code "97") (name "unconnected-(U4-SDA2{slash}U2RX{slash}RF4-Pad31)") (class "Default")
      (node (ref "U4") (pin "31") (pinfunction "SDA2/U2RX/RF4_31") (pintype "bidirectional"))
    )
    (net (code "98") (name "unconnected-(U4-SDI2{slash}CN9{slash}RG7-Pad5)") (class "Default")
      (node (ref "U4") (pin "5") (pinfunction "SDI2/CN9/RG7_5") (pintype "bidirectional"))
    )
    (net (code "99") (name "unconnected-(U4-SDO2{slash}CN10{slash}RG8-Pad6)") (class "Default")
      (node (ref "U4") (pin "6") (pinfunction "SDO2/CN10/RG8_6") (pintype "bidirectional"))
    )
    (net (code "100") (name "unconnected-(U4-SS2{slash}CN11{slash}RG9-Pad8)") (class "Default")
      (node (ref "U4") (pin "8") (pinfunction "SS2/CN11/RG9_8") (pintype "bidirectional"))
    )
    (net (code "101") (name "unconnected-(U4-T1CK{slash}CN0{slash}RC14-Pad48)") (class "Default")
      (node (ref "U4") (pin "48") (pinfunction "T1CK/CN0/RC14_48") (pintype "bidirectional"))
    )
    (net (code "102") (name "unconnected-(U4-T4CK{slash}CN1{slash}RC13-Pad47)") (class "Default")
      (node (ref "U4") (pin "47") (pinfunction "T4CK/CN1/RC13_47") (pintype "bidirectional"))
    )
  )
)
